# CurrentSensingSM.net
KiCad netlist of a schematic drawn in Altium Designer
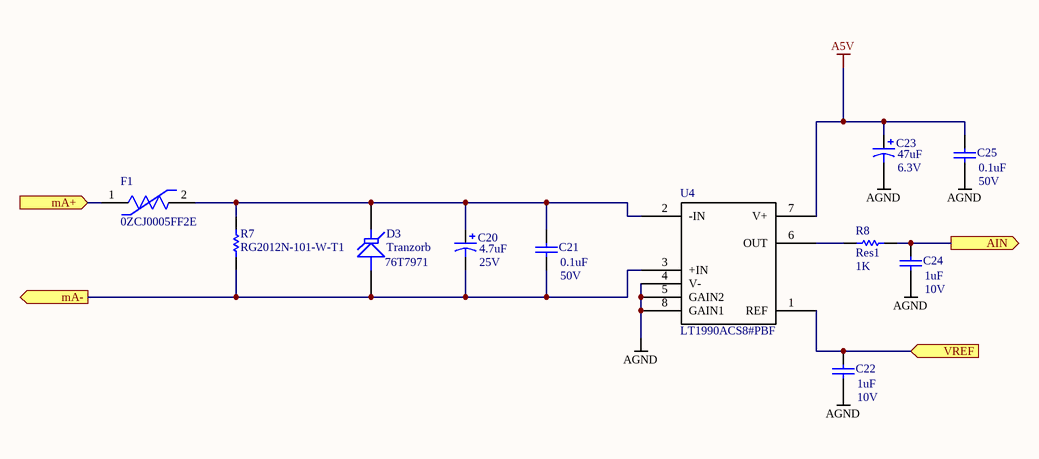
[diagram p0: CurrentSensingSM.SchDoc]

(export (version "E")
  (design (tool "Eeschema 10.0.6"))
  (components
    (comp (ref "C20")
      (value "4.7uF")
      (footprint "RB7.6-15")
      (description "Polarized Capacitor (Radial)")
      (fields
        (field (name "VOLTAGE RATING") "25V")
        (field (name "Comment") "Cap Pol1")
        (field (name "PUBLISHER") "Altium Limited")
      )
      (libsource (lib "Miscellaneous Devices") (part "Cap Pol1"))
    )
    (comp (ref "C21")
      (value "0.1uF")
      (footprint "RAD-0.3")
      (description "Capacitor")
      (fields
        (field (name "VOLTAGE RATING") "50V")
        (field (name "Comment") "Cap")
        (field (name "PUBLISHER") "Altium Limited")
      )
      (libsource (lib "Miscellaneous Devices") (part "Cap"))
    )
    (comp (ref "C22")
      (value "1uF")
      (footprint "RAD-0.3")
      (description "Capacitor")
      (fields
        (field (name "VOLTAGE RATING") "10V")
        (field (name "Comment") "Cap")
        (field (name "PUBLISHER") "Altium Limited")
      )
      (libsource (lib "Miscellaneous Devices") (part "Cap"))
    )
    (comp (ref "C23")
      (value "47uF")
      (footprint "RB7.6-15")
      (description "Polarized Capacitor (Radial)")
      (fields
        (field (name "VOLTAGE RATING") "6.3V")
        (field (name "Comment") "Cap Pol1")
        (field (name "PUBLISHER") "Altium Limited")
      )
      (libsource (lib "Miscellaneous Devices") (part "Cap Pol1"))
    )
    (comp (ref "C24")
      (value "1uF")
      (footprint "RAD-0.3")
      (description "Capacitor")
      (fields
        (field (name "VOLTAGE RATING") "10V")
        (field (name "Comment") "Cap")
        (field (name "PUBLISHER") "Altium Limited")
      )
      (libsource (lib "Miscellaneous Devices") (part "Cap"))
    )
    (comp (ref "C25")
      (value "0.1uF")
      (footprint "RAD-0.3")
      (description "Capacitor")
      (fields
        (field (name "VOLTAGE RATING") "50V")
        (field (name "Comment") "Cap")
        (field (name "PUBLISHER") "Altium Limited")
      )
      (libsource (lib "Miscellaneous Devices") (part "Cap"))
    )
    (comp (ref "D3")
      (value "Tranzorb")
      (footprint "SZ1SMB36CAT3G")
      (description "1SMB Series 600 W 36 V Bi-Directional Surface Mount TVS Diode - DO-214AA")
      (fields
        (field (name "SUPPLIER PART NUMBER 1") "76T7971")
        (field (name "MANUFACTURER") "ON Semiconductor")
        (field (name "MANUFACTURER PART NUMBER") "SZ1SMB36CAT3G")
        (field (name "PUBLISHER") "Altium Limited")
      )
      (libsource (lib "Miscellaneous Devices") (part "Tranzorb"))
    )
    (comp (ref "F1")
      (value "0ZCJ0005FF2E")
      (footprint "FP-0ZCJ0005FF2E-MFG")
      (description "PTC RESET FUSE 60V 50MA 1206")
      (libsource (lib "Altium Content Vault") (part "fdf083d5f6389a9a1c4e51137f46658"))
    )
    (comp (ref "R7")
      (value "RG2012N-101-W-T1")
      (footprint "RESC2013X50X40ML20T20")
      (fields (field (name "MANUFACTURER") "Susumu"))
      (libsource (lib "Altium Content Vault") (part "RES"))
    )
    (comp (ref "R8")
      (value "Res1")
      (footprint "AXIAL-0.3")
      (description "Resistor")
      (fields (field (name "ALTIUM_VALUE") "1K") (field (name "PUBLISHER") "Altium Limited"))
      (libsource (lib "Miscellaneous Devices") (part "Res1"))
    )
    (comp (ref "U4")
      (value "LT1990ACS8#PBF")
      (footprint "LT1990ACS8-PBF")
      (libsource (lib "Parts") (part "LT1990ACS8#PBF"))
    )
  )
  (nets
    (net (code "1") (name "/AIN") (class "Default")
      (node (ref "C24") (pin "2") (pinfunction "2_2") (pintype "passive"))
      (node (ref "R8") (pin "2") (pinfunction "2_2") (pintype "passive"))
    )
    (net (code "2") (name "/VREF") (class "Default")
      (node (ref "C22") (pin "2") (pinfunction "2_2") (pintype "passive"))
      (node (ref "U4") (pin "1") (pinfunction "REF_1") (pintype "passive"))
    )
    (net (code "3") (name "/mA+") (class "Default")
      (node (ref "F1") (pin "1") (pinfunction "1_1") (pintype "passive"))
    )
    (net (code "4") (name "/mA-") (class "Default")
      (node (ref "C20") (pin "2") (pinfunction "2_2") (pintype "passive"))
      (node (ref "C21") (pin "1") (pinfunction "1_1") (pintype "passive"))
      (node (ref "D3") (pin "1") (pinfunction "A_1") (pintype "passive"))
      (node (ref "R7") (pin "1") (pinfunction "1_1") (pintype "passive"))
      (node (ref "U4") (pin "3") (pinfunction "+IN_3") (pintype "passive"))
    )
    (net (code "5") (name "A5V") (class "Default")
      (node (ref "C23") (pin "1") (pinfunction "1_1") (pintype "passive"))
      (node (ref "C25") (pin "2") (pinfunction "2_2") (pintype "passive"))
      (node (ref "U4") (pin "7") (pinfunction "V+_7") (pintype "passive"))
    )
    (net (code "6") (name "AGND") (class "Default")
      (node (ref "C22") (pin "1") (pinfunction "1_1") (pintype "passive"))
      (node (ref "C23") (pin "2") (pinfunction "2_2") (pintype "passive"))
      (node (ref "C24") (pin "1") (pinfunction "1_1") (pintype "passive"))
      (node (ref "C25") (pin "1") (pinfunction "1_1") (pintype "passive"))
      (node (ref "U4") (pin "4") (pinfunction "V-_4") (pintype "passive"))
      (node (ref "U4") (pin "5") (pinfunction "GAIN2_5") (pintype "passive"))
      (node (ref "U4") (pin "8") (pinfunction "GAIN1_8") (pintype "passive"))
    )
    (net (code "7") (name "Net-(D3-K)") (class "Default")
      (node (ref "C20") (pin "1") (pinfunction "1_1") (pintype "passive"))
      (node (ref "C21") (pin "2") (pinfunction "2_2") (pintype "passive"))
      (node (ref "D3") (pin "2") (pinfunction "K_2") (pintype "passive"))
      (node (ref "F1") (pin "2") (pinfunction "2_2") (pintype "passive"))
      (node (ref "R7") (pin "2") (pinfunction "2_2") (pintype "passive"))
      (node (ref "U4") (pin "2") (pinfunction "-IN_2") (pintype "passive"))
    )
    (net (code "8") (name "Net-(U4-OUT)") (class "Default")
      (node (ref "R8") (pin "1") (pinfunction "1_1") (pintype "passive"))
      (node (ref "U4") (pin "6") (pinfunction "OUT_6") (pintype "passive"))
    )
  )
)
